# 2_MCU.net
KiCad netlist of a schematic drawn in Altium Designer
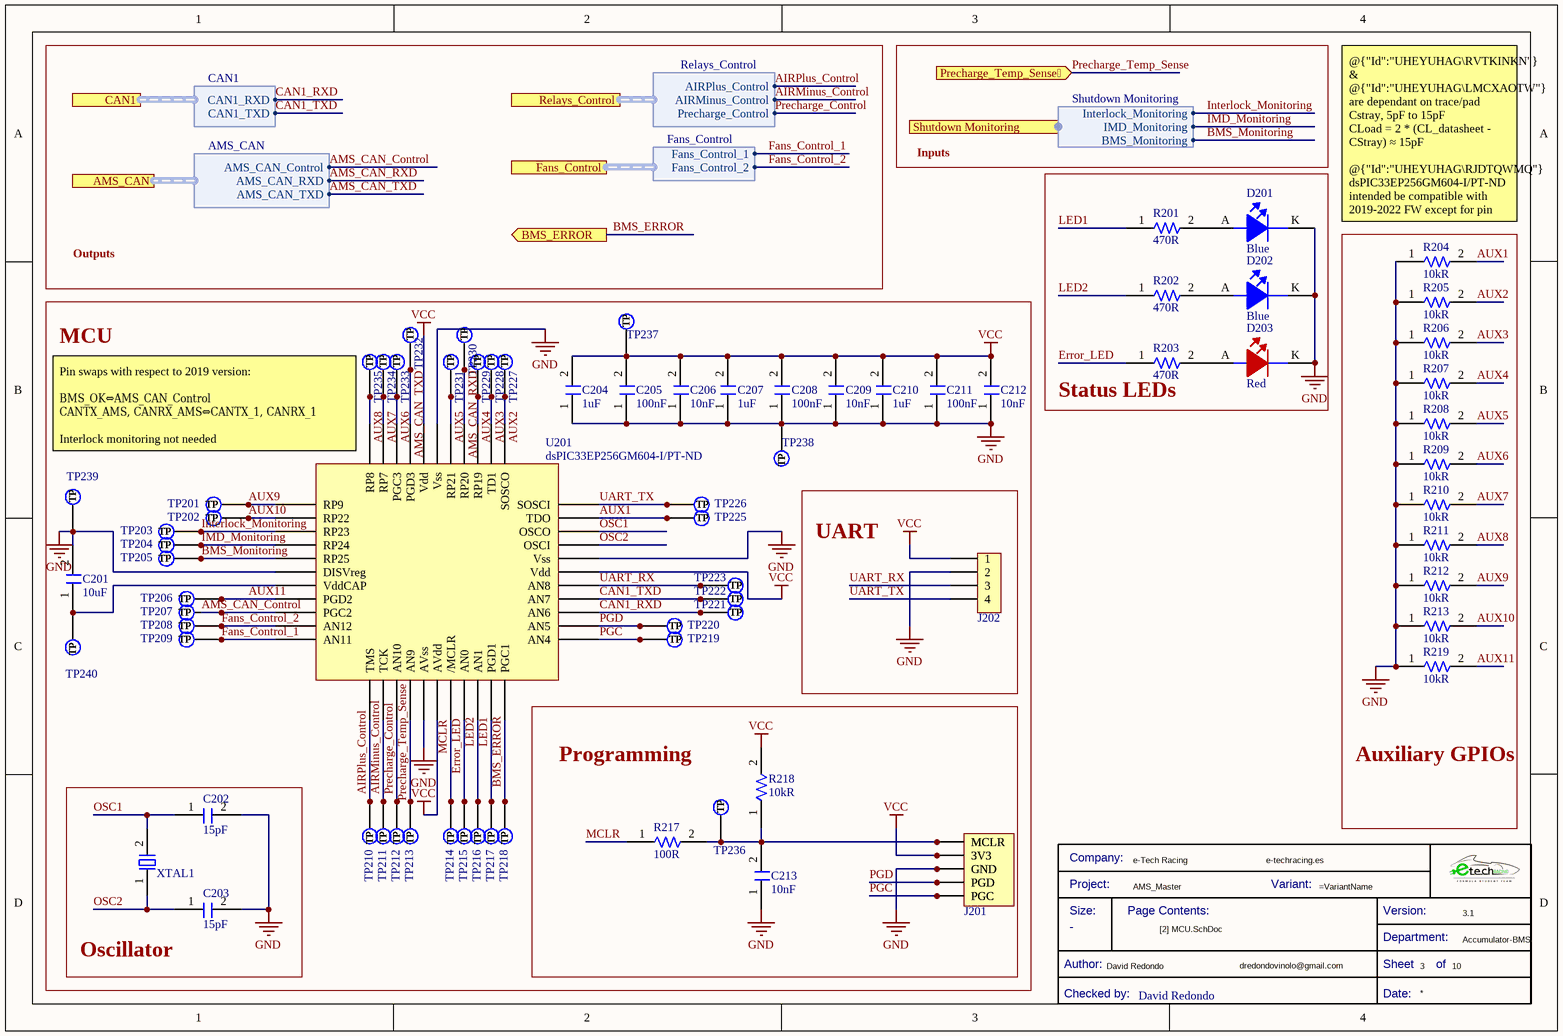
[diagram p0: [2] MCU.SchDoc]

(export (version "E")
  (design (tool "Eeschema 10.0.6"))
  (components
    (comp (ref "C201")
      (value "885012208018")
      (footprint "C1206FNPC-RW")
      (description "Cap, 10ΜF, 10V, 10%, X7R, 1206")
      (fields
        (field (name "TOLERANCE") "10%")
        (field (name "CAPACITANCE") "10uF")
        (field (name ".CREATOR") "GP")
      )
      (libsource (lib "Passives") (part "C10u-10V-1206FNPC-X7R"))
    )
    (comp (ref "C202")
      (value "885012007052")
      (footprint "C0805FNPC-R")
      (description "Cap, 15PF, 50V, 5%, C0G/NP0, 0805")
      (fields
        (field (name "TOLERANCE") "5%")
        (field (name "CAPACITANCE") "15pF")
        (field (name ".CREATOR") "DR")
      )
      (libsource (lib "Passives") (part "C15p-50V-0805FNPC-NP0"))
    )
    (comp (ref "C203")
      (value "885012007052")
      (footprint "C0805FNPC-R")
      (description "Cap, 15PF, 50V, 5%, C0G/NP0, 0805")
      (fields
        (field (name "TOLERANCE") "5%")
        (field (name "CAPACITANCE") "15pF")
        (field (name ".CREATOR") "DR")
      )
      (libsource (lib "Passives") (part "C15p-50V-0805FNPC-NP0"))
    )
    (comp (ref "C204")
      (value "885012207103")
      (footprint "C0805FNPC-R")
      (fields
        (field (name "TOLERANCE") "10%")
        (field (name "CAPACITANCE") "1uF")
        (field (name ".CREATOR") "GP")
      )
      (libsource (lib "Passives") (part "C1u-50V-0805FNPC-X7R"))
    )
    (comp (ref "C205")
      (value "885012207098")
      (footprint "C0805FNPC-R")
      (description "Cap, 0.1ΜF, 50V, 10%, X7R, 0805")
      (fields
        (field (name "TOLERANCE") "10%")
        (field (name "CAPACITANCE") "100nF")
        (field (name ".CREATOR") "DR")
      )
      (libsource (lib "Passives") (part "C100n-50V-0805FNPC-X7R"))
    )
    (comp (ref "C206")
      (value "885012207092")
      (footprint "C0805FNPC-R")
      (description "Cap, 0.01ΜF, 50V, 10%, X7R, 0805")
      (fields
        (field (name "TOLERANCE") "10%")
        (field (name "CAPACITANCE") "10nF")
        (field (name ".CREATOR") "DR")
      )
      (libsource (lib "Passives") (part "C10n-50V-0805FNPC-X7R"))
    )
    (comp (ref "C207")
      (value "885012207103")
      (footprint "C0805FNPC-R")
      (fields
        (field (name "TOLERANCE") "10%")
        (field (name "CAPACITANCE") "1uF")
        (field (name ".CREATOR") "GP")
      )
      (libsource (lib "Passives") (part "C1u-50V-0805FNPC-X7R"))
    )
    (comp (ref "C208")
      (value "885012207098")
      (footprint "C0805FNPC-R")
      (description "Cap, 0.1ΜF, 50V, 10%, X7R, 0805")
      (fields
        (field (name "TOLERANCE") "10%")
        (field (name "CAPACITANCE") "100nF")
        (field (name ".CREATOR") "DR")
      )
      (libsource (lib "Passives") (part "C100n-50V-0805FNPC-X7R"))
    )
    (comp (ref "C209")
      (value "885012207092")
      (footprint "C0805FNPC-R")
      (description "Cap, 0.01ΜF, 50V, 10%, X7R, 0805")
      (fields
        (field (name "TOLERANCE") "10%")
        (field (name "CAPACITANCE") "10nF")
        (field (name ".CREATOR") "DR")
      )
      (libsource (lib "Passives") (part "C10n-50V-0805FNPC-X7R"))
    )
    (comp (ref "C210")
      (value "885012207103")
      (footprint "C0805FNPC-R")
      (fields
        (field (name "TOLERANCE") "10%")
        (field (name "CAPACITANCE") "1uF")
        (field (name ".CREATOR") "GP")
      )
      (libsource (lib "Passives") (part "C1u-50V-0805FNPC-X7R"))
    )
    (comp (ref "C211")
      (value "885012207098")
      (footprint "C0805FNPC-R")
      (description "Cap, 0.1ΜF, 50V, 10%, X7R, 0805")
      (fields
        (field (name "TOLERANCE") "10%")
        (field (name "CAPACITANCE") "100nF")
        (field (name ".CREATOR") "DR")
      )
      (libsource (lib "Passives") (part "C100n-50V-0805FNPC-X7R"))
    )
    (comp (ref "C212")
      (value "885012207092")
      (footprint "C0805FNPC-R")
      (description "Cap, 0.01ΜF, 50V, 10%, X7R, 0805")
      (fields
        (field (name "TOLERANCE") "10%")
        (field (name "CAPACITANCE") "10nF")
        (field (name ".CREATOR") "DR")
      )
      (libsource (lib "Passives") (part "C10n-50V-0805FNPC-X7R"))
    )
    (comp (ref "C213")
      (value "885012207092")
      (footprint "C0805FNPC-R")
      (description "Cap, 0.01ΜF, 50V, 10%, X7R, 0805")
      (fields
        (field (name "TOLERANCE") "10%")
        (field (name "CAPACITANCE") "10nF")
        (field (name ".CREATOR") "DR")
      )
      (libsource (lib "Passives") (part "C10n-50V-0805FNPC-X7R"))
    )
    (comp (ref "D201")
      (value "150080BS75000")
      (footprint "LED_0805_WE")
      (description "LED BLUE CLEAR 0805 SMD")
      (fields (field (name "COLOR") "Blue") (field (name ".CREATOR") "GP"))
      (libsource (lib "Semiconductor") (part "LEDBS-0805-145"))
    )
    (comp (ref "D202")
      (value "150080BS75000")
      (footprint "LED_0805_WE")
      (description "LED BLUE CLEAR 0805 SMD")
      (fields (field (name "COLOR") "Blue") (field (name ".CREATOR") "GP"))
      (libsource (lib "Semiconductor") (part "LEDBS-0805-145"))
    )
    (comp (ref "D203")
      (value "150080RS75000")
      (footprint "LED_0805_WE")
      (description "0805(H=0.8mm) 红色 高亮 λD=625nm VF=2V IF=30mA PD=72mW")
      (fields (field (name "COLOR") "Red") (field (name ".CREATOR") "DR"))
      (libsource (lib "Semiconductor") (part "LEDRS-0805-150"))
    )
    (comp (ref "J201")
      (value "61300511121")
      (footprint "J_PinHeader_1x5")
      (description "THT Vertical Pin Header WR-PHD, Pitch 2.54 mm, Single Row, 5 pins")
      (fields (field (name "MANUFACTURER") "Molex") (field (name ".CREATOR") "GP"))
      (libsource (lib "Electromechanical") (part "J_Pickit3"))
    )
    (comp (ref "J202")
      (value "61300411121")
      (footprint "J_PinHeader_1x4")
      (description "CONN HEADER 4 POS 2.54")
      (fields (field (name ".CREATOR") "AC"))
      (libsource (lib "Electromechanical") (part "J_UART"))
    )
    (comp (ref "R201")
      (value "CR0805-FX-4700GLF")
      (footprint "R0805FTK")
      (description "Res Thick Film 0805 470 Ohm 1% 1/8W ±100ppm/°C Molded SMD SMD Paper Tape on Plastic Reel")
      (fields
        (field (name "TOLERANCE") "1%")
        (field (name "RESISTANCE") "470R")
        (field (name ".CREATOR") "DR")
      )
      (libsource (lib "Passives") (part "R470-0805FTK"))
    )
    (comp (ref "R202")
      (value "CR0805-FX-4700GLF")
      (footprint "R0805FTK")
      (description "Res Thick Film 0805 470 Ohm 1% 1/8W ±100ppm/°C Molded SMD SMD Paper Tape on Plastic Reel")
      (fields
        (field (name "TOLERANCE") "1%")
        (field (name "RESISTANCE") "470R")
        (field (name ".CREATOR") "DR")
      )
      (libsource (lib "Passives") (part "R470-0805FTK"))
    )
    (comp (ref "R203")
      (value "CR0805-FX-4700GLF")
      (footprint "R0805FTK")
      (description "Res Thick Film 0805 470 Ohm 1% 1/8W ±100ppm/°C Molded SMD SMD Paper Tape on Plastic Reel")
      (fields
        (field (name "TOLERANCE") "1%")
        (field (name "RESISTANCE") "470R")
        (field (name ".CREATOR") "DR")
      )
      (libsource (lib "Passives") (part "R470-0805FTK"))
    )
    (comp (ref "R204")
      (value "CR0805-JW-103ELF")
      (footprint "R0805FTK")
      (fields
        (field (name "TOLERANCE") "5%")
        (field (name "RESISTANCE") "10kR")
        (field (name ".CREATOR") "DR")
      )
      (libsource (lib "Passives") (part "R10k-0805FTK"))
    )
    (comp (ref "R205")
      (value "CR0805-JW-103ELF")
      (footprint "R0805FTK")
      (fields
        (field (name "TOLERANCE") "5%")
        (field (name "RESISTANCE") "10kR")
        (field (name ".CREATOR") "DR")
      )
      (libsource (lib "Passives") (part "R10k-0805FTK"))
    )
    (comp (ref "R206")
      (value "CR0805-JW-103ELF")
      (footprint "R0805FTK")
      (fields
        (field (name "TOLERANCE") "5%")
        (field (name "RESISTANCE") "10kR")
        (field (name ".CREATOR") "DR")
      )
      (libsource (lib "Passives") (part "R10k-0805FTK"))
    )
    (comp (ref "R207")
      (value "CR0805-JW-103ELF")
      (footprint "R0805FTK")
      (fields
        (field (name "TOLERANCE") "5%")
        (field (name "RESISTANCE") "10kR")
        (field (name ".CREATOR") "DR")
      )
      (libsource (lib "Passives") (part "R10k-0805FTK"))
    )
    (comp (ref "R208")
      (value "CR0805-JW-103ELF")
      (footprint "R0805FTK")
      (fields
        (field (name "TOLERANCE") "5%")
        (field (name "RESISTANCE") "10kR")
        (field (name ".CREATOR") "DR")
      )
      (libsource (lib "Passives") (part "R10k-0805FTK"))
    )
    (comp (ref "R209")
      (value "CR0805-JW-103ELF")
      (footprint "R0805FTK")
      (fields
        (field (name "TOLERANCE") "5%")
        (field (name "RESISTANCE") "10kR")
        (field (name ".CREATOR") "DR")
      )
      (libsource (lib "Passives") (part "R10k-0805FTK"))
    )
    (comp (ref "R210")
      (value "CR0805-JW-103ELF")
      (footprint "R0805FTK")
      (fields
        (field (name "TOLERANCE") "5%")
        (field (name "RESISTANCE") "10kR")
        (field (name ".CREATOR") "DR")
      )
      (libsource (lib "Passives") (part "R10k-0805FTK"))
    )
    (comp (ref "R211")
      (value "CR0805-JW-103ELF")
      (footprint "R0805FTK")
      (fields
        (field (name "TOLERANCE") "5%")
        (field (name "RESISTANCE") "10kR")
        (field (name ".CREATOR") "DR")
      )
      (libsource (lib "Passives") (part "R10k-0805FTK"))
    )
    (comp (ref "R212")
      (value "CR0805-JW-103ELF")
      (footprint "R0805FTK")
      (fields
        (field (name "TOLERANCE") "5%")
        (field (name "RESISTANCE") "10kR")
        (field (name ".CREATOR") "DR")
      )
      (libsource (lib "Passives") (part "R10k-0805FTK"))
    )
    (comp (ref "R213")
      (value "CR0805-JW-103ELF")
      (footprint "R0805FTK")
      (fields
        (field (name "TOLERANCE") "5%")
        (field (name "RESISTANCE") "10kR")
        (field (name ".CREATOR") "DR")
      )
      (libsource (lib "Passives") (part "R10k-0805FTK"))
    )
    (comp (ref "R217")
      (value "CR0805-FX-1000ELF")
      (footprint "R0805FTK")
      (description "Res Thick Film 0805 100 Ohm 1% 1/8W ±100ppm/°C Molded SMD SMD Paper Tape on Plastic Reel")
      (fields
        (field (name "TOLERANCE") "1%")
        (field (name "RESISTANCE") "100R")
        (field (name ".CREATOR") "DR")
      )
      (libsource (lib "Passives") (part "R100-0805FTK"))
    )
    (comp (ref "R218")
      (value "CR0805-JW-103ELF")
      (footprint "R0805FTK")
      (fields
        (field (name "TOLERANCE") "5%")
        (field (name "RESISTANCE") "10kR")
        (field (name ".CREATOR") "DR")
      )
      (libsource (lib "Passives") (part "R10k-0805FTK"))
    )
    (comp (ref "R219")
      (value "CR0805-JW-103ELF")
      (footprint "R0805FTK")
      (fields
        (field (name "TOLERANCE") "5%")
        (field (name "RESISTANCE") "10kR")
        (field (name ".CREATOR") "DR")
      )
      (libsource (lib "Passives") (part "R10k-0805FTK"))
    )
    (comp (ref "TP201")
      (value "TestPoint")
      (footprint "TestPoint")
      (description "Test Point 1x1 mm")
      (fields (field (name ".CREATOR") "GP") (field (name ".PCBCHECK") "GP") (field (name ".SCHCHECK") "GP"))
      (libsource (lib "e-Tech_Racing") (part "TestPoint"))
    )
    (comp (ref "TP202")
      (value "TestPoint")
      (footprint "TestPoint")
      (description "Test Point 1x1 mm")
      (fields (field (name ".CREATOR") "GP") (field (name ".PCBCHECK") "GP") (field (name ".SCHCHECK") "GP"))
      (libsource (lib "e-Tech_Racing") (part "TestPoint"))
    )
    (comp (ref "TP203")
      (value "TestPoint")
      (footprint "TestPoint")
      (description "Test Point 1x1 mm")
      (fields (field (name ".CREATOR") "GP") (field (name ".PCBCHECK") "GP") (field (name ".SCHCHECK") "GP"))
      (libsource (lib "e-Tech_Racing") (part "TestPoint"))
    )
    (comp (ref "TP204")
      (value "TestPoint")
      (footprint "TestPoint")
      (description "Test Point 1x1 mm")
      (fields (field (name ".CREATOR") "GP") (field (name ".PCBCHECK") "GP") (field (name ".SCHCHECK") "GP"))
      (libsource (lib "e-Tech_Racing") (part "TestPoint"))
    )
    (comp (ref "TP205")
      (value "TestPoint")
      (footprint "TestPoint")
      (description "Test Point 1x1 mm")
      (fields (field (name ".CREATOR") "GP") (field (name ".PCBCHECK") "GP") (field (name ".SCHCHECK") "GP"))
      (libsource (lib "e-Tech_Racing") (part "TestPoint"))
    )
    (comp (ref "TP206")
      (value "TestPoint")
      (footprint "TestPoint")
      (description "Test Point 1x1 mm")
      (fields (field (name ".CREATOR") "GP") (field (name ".PCBCHECK") "GP") (field (name ".SCHCHECK") "GP"))
      (libsource (lib "e-Tech_Racing") (part "TestPoint"))
    )
    (comp (ref "TP207")
      (value "TestPoint")
      (footprint "TestPoint")
      (description "Test Point 1x1 mm")
      (fields (field (name ".CREATOR") "GP") (field (name ".PCBCHECK") "GP") (field (name ".SCHCHECK") "GP"))
      (libsource (lib "e-Tech_Racing") (part "TestPoint"))
    )
    (comp (ref "TP208")
      (value "TestPoint")
      (footprint "TestPoint")
      (description "Test Point 1x1 mm")
      (fields (field (name ".CREATOR") "GP") (field (name ".PCBCHECK") "GP") (field (name ".SCHCHECK") "GP"))
      (libsource (lib "e-Tech_Racing") (part "TestPoint"))
    )
    (comp (ref "TP209")
      (value "TestPoint")
      (footprint "TestPoint")
      (description "Test Point 1x1 mm")
      (fields (field (name ".CREATOR") "GP") (field (name ".PCBCHECK") "GP") (field (name ".SCHCHECK") "GP"))
      (libsource (lib "e-Tech_Racing") (part "TestPoint"))
    )
    (comp (ref "TP210")
      (value "TestPoint")
      (footprint "TestPoint")
      (description "Test Point 1x1 mm")
      (fields (field (name ".CREATOR") "GP") (field (name ".PCBCHECK") "GP") (field (name ".SCHCHECK") "GP"))
      (libsource (lib "e-Tech_Racing") (part "TestPoint"))
    )
    (comp (ref "TP211")
      (value "TestPoint")
      (footprint "TestPoint")
      (description "Test Point 1x1 mm")
      (fields (field (name ".CREATOR") "GP") (field (name ".PCBCHECK") "GP") (field (name ".SCHCHECK") "GP"))
      (libsource (lib "e-Tech_Racing") (part "TestPoint"))
    )
    (comp (ref "TP212")
      (value "TestPoint")
      (footprint "TestPoint")
      (description "Test Point 1x1 mm")
      (fields (field (name ".CREATOR") "GP") (field (name ".PCBCHECK") "GP") (field (name ".SCHCHECK") "GP"))
      (libsource (lib "e-Tech_Racing") (part "TestPoint"))
    )
    (comp (ref "TP213")
      (value "TestPoint")
      (footprint "TestPoint")
      (description "Test Point 1x1 mm")
      (fields (field (name ".CREATOR") "GP") (field (name ".PCBCHECK") "GP") (field (name ".SCHCHECK") "GP"))
      (libsource (lib "e-Tech_Racing") (part "TestPoint"))
    )
    (comp (ref "TP214")
      (value "TestPoint")
      (footprint "TestPoint")
      (description "Test Point 1x1 mm")
      (fields (field (name ".CREATOR") "GP") (field (name ".PCBCHECK") "GP") (field (name ".SCHCHECK") "GP"))
      (libsource (lib "e-Tech_Racing") (part "TestPoint"))
    )
    (comp (ref "TP215")
      (value "TestPoint")
      (footprint "TestPoint")
      (description "Test Point 1x1 mm")
      (fields (field (name ".CREATOR") "GP") (field (name ".PCBCHECK") "GP") (field (name ".SCHCHECK") "GP"))
      (libsource (lib "e-Tech_Racing") (part "TestPoint"))
    )
    (comp (ref "TP216")
      (value "TestPoint")
      (footprint "TestPoint")
      (description "Test Point 1x1 mm")
      (fields (field (name ".CREATOR") "GP") (field (name ".PCBCHECK") "GP") (field (name ".SCHCHECK") "GP"))
      (libsource (lib "e-Tech_Racing") (part "TestPoint"))
    )
    (comp (ref "TP217")
      (value "TestPoint")
      (footprint "TestPoint")
      (description "Test Point 1x1 mm")
      (fields (field (name ".CREATOR") "GP") (field (name ".PCBCHECK") "GP") (field (name ".SCHCHECK") "GP"))
      (libsource (lib "e-Tech_Racing") (part "TestPoint"))
    )
    (comp (ref "TP218")
      (value "TestPoint")
      (footprint "TestPoint")
      (description "Test Point 1x1 mm")
      (fields (field (name ".CREATOR") "GP") (field (name ".PCBCHECK") "GP") (field (name ".SCHCHECK") "GP"))
      (libsource (lib "e-Tech_Racing") (part "TestPoint"))
    )
    (comp (ref "TP219")
      (value "TestPoint")
      (footprint "TestPoint")
      (description "Test Point 1x1 mm")
      (fields (field (name ".CREATOR") "GP") (field (name ".PCBCHECK") "GP") (field (name ".SCHCHECK") "GP"))
      (libsource (lib "e-Tech_Racing") (part "TestPoint"))
    )
    (comp (ref "TP220")
      (value "TestPoint")
      (footprint "TestPoint")
      (description "Test Point 1x1 mm")
      (fields (field (name ".CREATOR") "GP") (field (name ".PCBCHECK") "GP") (field (name ".SCHCHECK") "GP"))
      (libsource (lib "e-Tech_Racing") (part "TestPoint"))
    )
    (comp (ref "TP221")
      (value "TestPoint")
      (footprint "TestPoint")
      (description "Test Point 1x1 mm")
      (fields (field (name ".CREATOR") "GP") (field (name ".PCBCHECK") "GP") (field (name ".SCHCHECK") "GP"))
      (libsource (lib "e-Tech_Racing") (part "TestPoint"))
    )
    (comp (ref "TP222")
      (value "TestPoint")
      (footprint "TestPoint")
      (description "Test Point 1x1 mm")
      (fields (field (name ".CREATOR") "GP") (field (name ".PCBCHECK") "GP") (field (name ".SCHCHECK") "GP"))
      (libsource (lib "e-Tech_Racing") (part "TestPoint"))
    )
    (comp (ref "TP223")
      (value "TestPoint")
      (footprint "TestPoint")
      (description "Test Point 1x1 mm")
      (fields (field (name ".CREATOR") "GP") (field (name ".PCBCHECK") "GP") (field (name ".SCHCHECK") "GP"))
      (libsource (lib "e-Tech_Racing") (part "TestPoint"))
    )
    (comp (ref "TP225")
      (value "TestPoint")
      (footprint "TestPoint")
      (description "Test Point 1x1 mm")
      (fields (field (name ".CREATOR") "GP") (field (name ".PCBCHECK") "GP") (field (name ".SCHCHECK") "GP"))
      (libsource (lib "e-Tech_Racing") (part "TestPoint"))
    )
    (comp (ref "TP226")
      (value "TestPoint")
      (footprint "TestPoint")
      (description "Test Point 1x1 mm")
      (fields (field (name ".CREATOR") "GP") (field (name ".PCBCHECK") "GP") (field (name ".SCHCHECK") "GP"))
      (libsource (lib "e-Tech_Racing") (part "TestPoint"))
    )
    (comp (ref "TP227")
      (value "TestPoint")
      (footprint "TestPoint")
      (description "Test Point 1x1 mm")
      (fields (field (name ".CREATOR") "GP") (field (name ".PCBCHECK") "GP") (field (name ".SCHCHECK") "GP"))
      (libsource (lib "e-Tech_Racing") (part "TestPoint"))
    )
    (comp (ref "TP228")
      (value "TestPoint")
      (footprint "TestPoint")
      (description "Test Point 1x1 mm")
      (fields (field (name ".CREATOR") "GP") (field (name ".PCBCHECK") "GP") (field (name ".SCHCHECK") "GP"))
      (libsource (lib "e-Tech_Racing") (part "TestPoint"))
    )
    (comp (ref "TP229")
      (value "TestPoint")
      (footprint "TestPoint")
      (description "Test Point 1x1 mm")
      (fields (field (name ".CREATOR") "GP") (field (name ".PCBCHECK") "GP") (field (name ".SCHCHECK") "GP"))
      (libsource (lib "e-Tech_Racing") (part "TestPoint"))
    )
    (comp (ref "TP230")
      (value "TestPoint")
      (footprint "TestPoint")
      (description "Test Point 1x1 mm")
      (fields (field (name ".CREATOR") "GP") (field (name ".PCBCHECK") "GP") (field (name ".SCHCHECK") "GP"))
      (libsource (lib "e-Tech_Racing") (part "TestPoint"))
    )
    (comp (ref "TP231")
      (value "TestPoint")
      (footprint "TestPoint")
      (description "Test Point 1x1 mm")
      (fields (field (name ".CREATOR") "GP") (field (name ".PCBCHECK") "GP") (field (name ".SCHCHECK") "GP"))
      (libsource (lib "e-Tech_Racing") (part "TestPoint"))
    )
    (comp (ref "TP232")
      (value "TestPoint")
      (footprint "TestPoint")
      (description "Test Point 1x1 mm")
      (fields (field (name ".CREATOR") "GP") (field (name ".PCBCHECK") "GP") (field (name ".SCHCHECK") "GP"))
      (libsource (lib "e-Tech_Racing") (part "TestPoint"))
    )
    (comp (ref "TP233")
      (value "TestPoint")
      (footprint "TestPoint")
      (description "Test Point 1x1 mm")
      (fields (field (name ".CREATOR") "GP") (field (name ".PCBCHECK") "GP") (field (name ".SCHCHECK") "GP"))
      (libsource (lib "e-Tech_Racing") (part "TestPoint"))
    )
    (comp (ref "TP234")
      (value "TestPoint")
      (footprint "TestPoint")
      (description "Test Point 1x1 mm")
      (fields (field (name ".CREATOR") "GP") (field (name ".PCBCHECK") "GP") (field (name ".SCHCHECK") "GP"))
      (libsource (lib "e-Tech_Racing") (part "TestPoint"))
    )
    (comp (ref "TP235")
      (value "TestPoint")
      (footprint "TestPoint")
      (description "Test Point 1x1 mm")
      (fields (field (name ".CREATOR") "GP") (field (name ".PCBCHECK") "GP") (field (name ".SCHCHECK") "GP"))
      (libsource (lib "e-Tech_Racing") (part "TestPoint"))
    )
    (comp (ref "TP236")
      (value "TestPoint")
      (footprint "TestPoint")
      (description "Test Point 1x1 mm")
      (fields (field (name ".CREATOR") "GP") (field (name ".PCBCHECK") "GP") (field (name ".SCHCHECK") "GP"))
      (libsource (lib "e-Tech_Racing") (part "TestPoint"))
    )
    (comp (ref "TP237")
      (value "TestPoint")
      (footprint "TestPoint")
      (description "Test Point 1x1 mm")
      (fields (field (name ".CREATOR") "GP") (field (name ".PCBCHECK") "GP") (field (name ".SCHCHECK") "GP"))
      (libsource (lib "e-Tech_Racing") (part "TestPoint"))
    )
    (comp (ref "TP238")
      (value "TestPoint")
      (footprint "TestPoint")
      (description "Test Point 1x1 mm")
      (fields (field (name ".CREATOR") "GP") (field (name ".PCBCHECK") "GP") (field (name ".SCHCHECK") "GP"))
      (libsource (lib "e-Tech_Racing") (part "TestPoint"))
    )
    (comp (ref "TP239")
      (value "TestPoint")
      (footprint "TestPoint")
      (description "Test Point 1x1 mm")
      (fields (field (name ".CREATOR") "GP") (field (name ".PCBCHECK") "GP") (field (name ".SCHCHECK") "GP"))
      (libsource (lib "e-Tech_Racing") (part "TestPoint"))
    )
    (comp (ref "TP240")
      (value "TestPoint")
      (footprint "TestPoint")
      (description "Test Point 1x1 mm")
      (fields (field (name ".CREATOR") "GP") (field (name ".PCBCHECK") "GP") (field (name ".SCHCHECK") "GP"))
      (libsource (lib "e-Tech_Racing") (part "TestPoint"))
    )
    (comp (ref "U201")
      (value "dsPIC33EP256GM604-I/PT")
      (footprint "U_dsPIC33EP256GM604-I/PT")
      (description "16-bit MCU/DSC, 256 KB, 32768 Bytes, 70 MHz, 3 to 3.6V, TQFP-44, RoHS")
      (fields
        (field (name "SUPPLIER PART NUMBER 1") "dsPIC33EP256GM604-I/PT-ND")
        (field (name ".CREATOR") "DR")
      )
      (libsource (lib "Integrated circuits") (part "U_dsPIC33EP256GM604-I/PT"))
    )
    (comp (ref "XTAL1")
      (value "830028710")
      (footprint "XTAL20M_SMD")
      (description "830028710, 20 MHz")
      (fields (field (name "MANUFACTURER") "Würth Elektronik") (field (name ".CREATOR") "GP"))
      (libsource (lib "Passives") (part "XTAL20M_SMD"))
    )
  )
  (nets
    (net (code "7") (name "/AIRMinus_Control") (class "Default")
      (node (ref "TP211") (pin "1") (pinfunction "TP_1") (pintype "passive"))
      (node (ref "U201") (pin "13") (pinfunction "TCK_13") (pintype "passive"))
    )
    (net (code "8") (name "/AIRPlus_Control") (class "Default")
      (node (ref "TP210") (pin "1") (pinfunction "TP_1") (pintype "passive"))
      (node (ref "U201") (pin "12") (pinfunction "TMS_12") (pintype "passive"))
    )
    (net (code "9") (name "/AMS_CAN_Control") (class "Default")
      (node (ref "TP207") (pin "1") (pinfunction "TP_1") (pintype "passive"))
      (node (ref "U201") (pin "9") (pinfunction "PGC2_9") (pintype "passive"))
    )
    (net (code "10") (name "/AMS_CAN_RXD") (class "Default")
      (node (ref "TP230") (pin "1") (pinfunction "TP_1") (pintype "passive"))
      (node (ref "U201") (pin "37") (pinfunction "RP20_37") (pintype "passive"))
    )
    (net (code "11") (name "/AMS_CAN_TXD") (class "Default")
      (node (ref "TP232") (pin "1") (pinfunction "TP_1") (pintype "passive"))
      (node (ref "U201") (pin "41") (pinfunction "PGD3_41") (pintype "passive"))
    )
    (net (code "12") (name "/AUX1") (class "Default")
      (node (ref "R204") (pin "2") (pinfunction "2_2") (pintype "passive"))
      (node (ref "TP225") (pin "1") (pinfunction "TP_1") (pintype "passive"))
      (node (ref "U201") (pin "32") (pinfunction "TDO_32") (pintype "passive"))
    )
    (net (code "13") (name "/AUX2") (class "Default")
      (node (ref "R205") (pin "2") (pinfunction "2_2") (pintype "passive"))
      (node (ref "TP227") (pin "1") (pinfunction "TP_1") (pintype "passive"))
      (node (ref "U201") (pin "34") (pinfunction "SOSCO_34") (pintype "passive"))
    )
    (net (code "14") (name "/AUX3") (class "Default")
      (node (ref "R206") (pin "2") (pinfunction "2_2") (pintype "passive"))
      (node (ref "TP228") (pin "1") (pinfunction "TP_1") (pintype "passive"))
      (node (ref "U201") (pin "35") (pinfunction "TD1_35") (pintype "passive"))
    )
    (net (code "15") (name "/AUX4") (class "Default")
      (node (ref "R207") (pin "2") (pinfunction "2_2") (pintype "passive"))
      (node (ref "TP229") (pin "1") (pinfunction "TP_1") (pintype "passive"))
      (node (ref "U201") (pin "36") (pinfunction "RP19_36") (pintype "passive"))
    )
    (net (code "16") (name "/AUX5") (class "Default")
      (node (ref "R208") (pin "2") (pinfunction "2_2") (pintype "passive"))
      (node (ref "TP231") (pin "1") (pinfunction "TP_1") (pintype "passive"))
      (node (ref "U201") (pin "38") (pinfunction "RP21_38") (pintype "passive"))
    )
    (net (code "17") (name "/AUX6") (class "Default")
      (node (ref "R209") (pin "2") (pinfunction "2_2") (pintype "passive"))
      (node (ref "TP233") (pin "1") (pinfunction "TP_1") (pintype "passive"))
      (node (ref "U201") (pin "42") (pinfunction "PGC3_42") (pintype "passive"))
    )
    (net (code "18") (name "/AUX7") (class "Default")
      (node (ref "R210") (pin "2") (pinfunction "2_2") (pintype "passive"))
      (node (ref "TP234") (pin "1") (pinfunction "TP_1") (pintype "passive"))
      (node (ref "U201") (pin "43") (pinfunction "RP7_43") (pintype "passive"))
    )
    (net (code "19") (name "/AUX8") (class "Default")
      (node (ref "R211") (pin "2") (pinfunction "2_2") (pintype "passive"))
      (node (ref "TP235") (pin "1") (pinfunction "TP_1") (pintype "passive"))
      (node (ref "U201") (pin "44") (pinfunction "RP8_44") (pintype "passive"))
    )
    (net (code "20") (name "/AUX9") (class "Default")
      (node (ref "R212") (pin "2") (pinfunction "2_2") (pintype "passive"))
      (node (ref "TP201") (pin "1") (pinfunction "TP_1") (pintype "passive"))
      (node (ref "U201") (pin "1") (pinfunction "RP9_1") (pintype "passive"))
    )
    (net (code "21") (name "/AUX10") (class "Default")
      (node (ref "R213") (pin "2") (pinfunction "2_2") (pintype "passive"))
      (node (ref "TP202") (pin "1") (pinfunction "TP_1") (pintype "passive"))
      (node (ref "U201") (pin "2") (pinfunction "RP22_2") (pintype "passive"))
    )
    (net (code "22") (name "/AUX11") (class "Default")
      (node (ref "R219") (pin "2") (pinfunction "2_2") (pintype "passive"))
      (node (ref "TP206") (pin "1") (pinfunction "TP_1") (pintype "passive"))
      (node (ref "U201") (pin "8") (pinfunction "PGD2_8") (pintype "passive"))
    )
    (net (code "23") (name "/BMS_ERROR") (class "Default")
      (node (ref "TP218") (pin "1") (pinfunction "TP_1") (pintype "passive"))
      (node (ref "U201") (pin "22") (pinfunction "PGC1_22") (pintype "passive"))
    )
    (net (code "24") (name "/BMS_Monitoring") (class "Default")
      (node (ref "TP205") (pin "1") (pinfunction "TP_1") (pintype "passive"))
      (node (ref "U201") (pin "5") (pinfunction "RP25_5") (pintype "passive"))
    )
    (net (code "25") (name "/CAN1_RXD") (class "Default")
      (node (ref "TP221") (pin "1") (pinfunction "TP_1") (pintype "passive"))
      (node (ref "U201") (pin "25") (pinfunction "AN6_25") (pintype "passive"))
    )
    (net (code "26") (name "/CAN1_TXD") (class "Default")
      (node (ref "TP222") (pin "1") (pinfunction "TP_1") (pintype "passive"))
      (node (ref "U201") (pin "26") (pinfunction "AN7_26") (pintype "passive"))
    )
    (net (code "27") (name "/Error_LED") (class "Default")
      (node (ref "R203") (pin "1") (pinfunction "1_1") (pintype "passive"))
      (node (ref "TP215") (pin "1") (pinfunction "TP_1") (pintype "passive"))
      (node (ref "U201") (pin "19") (pinfunction "AN0_19") (pintype "passive"))
    )
    (net (code "28") (name "/Fans_Control_1") (class "Default")
      (node (ref "TP209") (pin "1") (pinfunction "TP_1") (pintype "passive"))
      (node (ref "U201") (pin "11") (pinfunction "AN11_11") (pintype "passive"))
    )
    (net (code "29") (name "/Fans_Control_2") (class "Default")
      (node (ref "TP208") (pin "1") (pinfunction "TP_1") (pintype "passive"))
      (node (ref "U201") (pin "10") (pinfunction "AN12_10") (pintype "passive"))
    )
    (net (code "30") (name "/IMD_Monitoring") (class "Default")
      (node (ref "TP204") (pin "1") (pinfunction "TP_1") (pintype "passive"))
      (node (ref "U201") (pin "4") (pinfunction "RP24_4") (pintype "passive"))
    )
    (net (code "31") (name "/Interlock_Monitoring") (class "Default")
      (node (ref "TP203") (pin "1") (pinfunction "TP_1") (pintype "passive"))
      (node (ref "U201") (pin "3") (pinfunction "RP23_3") (pintype "passive"))
    )
    (net (code "32") (name "/LED1") (class "Default")
      (node (ref "R201") (pin "1") (pinfunction "1_1") (pintype "passive"))
      (node (ref "TP217") (pin "1") (pinfunction "TP_1") (pintype "passive"))
      (node (ref "U201") (pin "21") (pinfunction "PGD1_21") (pintype "passive"))
    )
    (net (code "33") (name "/LED2") (class "Default")
      (node (ref "R202") (pin "1") (pinfunction "1_1") (pintype "passive"))
      (node (ref "TP216") (pin "1") (pinfunction "TP_1") (pintype "passive"))
      (node (ref "U201") (pin "20") (pinfunction "AN1_20") (pintype "passive"))
    )
    (net (code "34") (name "/MCLR") (class "Default")
      (node (ref "R217") (pin "1") (pinfunction "1_1") (pintype "passive"))
      (node (ref "TP214") (pin "1") (pinfunction "TP_1") (pintype "passive"))
      (node (ref "U201") (pin "18") (pinfunction "/MCLR_18") (pintype "passive"))
    )
    (net (code "35") (name "/OSC1") (class "Default")
      (node (ref "C202") (pin "1") (pinfunction "1_1") (pintype "passive"))
      (node (ref "U201") (pin "31") (pinfunction "OSCO_31") (pintype "passive"))
      (node (ref "XTAL1") (pin "2") (pinfunction "2_2") (pintype "passive"))
    )
    (net (code "36") (name "/OSC2") (class "Default")
      (node (ref "C203") (pin "1") (pinfunction "1_1") (pintype "passive"))
      (node (ref "U201") (pin "30") (pinfunction "OSCI_30") (pintype "passive"))
      (node (ref "XTAL1") (pin "1") (pinfunction "1_1") (pintype "passive"))
    )
    (net (code "37") (name "/PGC") (class "Default")
      (node (ref "J201") (pin "5") (pinfunction "PGC_5") (pintype "passive"))
      (node (ref "TP219") (pin "1") (pinfunction "TP_1") (pintype "passive"))
      (node (ref "U201") (pin "23") (pinfunction "AN4_23") (pintype "passive"))
    )
    (net (code "38") (name "/PGD") (class "Default")
      (node (ref "J201") (pin "4") (pinfunction "PGD_4") (pintype "passive"))
      (node (ref "TP220") (pin "1") (pinfunction "TP_1") (pintype "passive"))
      (node (ref "U201") (pin "24") (pinfunction "AN5_24") (pintype "passive"))
    )
    (net (code "39") (name "/Precharge_Control") (class "Default")
      (node (ref "TP212") (pin "1") (pinfunction "TP_1") (pintype "passive"))
      (node (ref "U201") (pin "14") (pinfunction "AN10_14") (pintype "passive"))
    )
    (net (code "40") (name "/Precharge_Temp_Sense") (class "Default")
      (node (ref "TP213") (pin "1") (pinfunction "TP_1") (pintype "passive"))
      (node (ref "U201") (pin "15") (pinfunction "AN9_15") (pintype "passive"))
    )
    (net (code "41") (name "/UART_RX") (class "Default")
      (node (ref "J202") (pin "3") (pinfunction "3_3") (pintype "passive"))
      (node (ref "TP223") (pin "1") (pinfunction "TP_1") (pintype "passive"))
      (node (ref "U201") (pin "27") (pinfunction "AN8_27") (pintype "passive"))
    )
    (net (code "42") (name "/UART_TX") (class "Default")
      (node (ref "J202") (pin "4") (pinfunction "4_4") (pintype "passive"))
      (node (ref "TP226") (pin "1") (pinfunction "TP_1") (pintype "passive"))
      (node (ref "U201") (pin "33") (pinfunction "SOSCI_33") (pintype "passive"))
    )
    (net (code "48") (name "GND") (class "Default")
      (node (ref "C201") (pin "2") (pinfunction "2_2") (pintype "passive"))
      (node (ref "C202") (pin "2") (pinfunction "2_2") (pintype "passive"))
      (node (ref "C203") (pin "2") (pinfunction "2_2") (pintype "passive"))
      (node (ref "C204") (pin "1") (pinfunction "1_1") (pintype "passive"))
      (node (ref "C205") (pin "1") (pinfunction "1_1") (pintype "passive"))
      (node (ref "C206") (pin "1") (pinfunction "1_1") (pintype "passive"))
      (node (ref "C207") (pin "1") (pinfunction "1_1") (pintype "passive"))
      (node (ref "C208") (pin "1") (pinfunction "1_1") (pintype "passive"))
      (node (ref "C209") (pin "1") (pinfunction "1_1") (pintype "passive"))
      (node (ref "C210") (pin "1") (pinfunction "1_1") (pintype "passive"))
      (node (ref "C211") (pin "1") (pinfunction "1_1") (pintype "passive"))
      (node (ref "C212") (pin "1") (pinfunction "1_1") (pintype "passive"))
      (node (ref "C213") (pin "1") (pinfunction "1_1") (pintype "passive"))
      (node (ref "D201") (pin "K") (pinfunction "K_K") (pintype "passive"))
      (node (ref "D202") (pin "K") (pinfunction "K_K") (pintype "passive"))
      (node (ref "D203") (pin "K") (pinfunction "K_K") (pintype "passive"))
      (node (ref "J201") (pin "3") (pinfunction "GND_3") (pintype "passive"))
      (node (ref "J202") (pin "2") (pinfunction "2_2") (pintype "passive"))
      (node (ref "R204") (pin "1") (pinfunction "1_1") (pintype "passive"))
      (node (ref "R205") (pin "1") (pinfunction "1_1") (pintype "passive"))
      (node (ref "R206") (pin "1") (pinfunction "1_1") (pintype "passive"))
      (node (ref "R207") (pin "1") (pinfunction "1_1") (pintype "passive"))
      (node (ref "R208") (pin "1") (pinfunction "1_1") (pintype "passive"))
      (node (ref "R209") (pin "1") (pinfunction "1_1") (pintype "passive"))
      (node (ref "R210") (pin "1") (pinfunction "1_1") (pintype "passive"))
      (node (ref "R211") (pin "1") (pinfunction "1_1") (pintype "passive"))
      (node (ref "R212") (pin "1") (pinfunction "1_1") (pintype "passive"))
      (node (ref "R213") (pin "1") (pinfunction "1_1") (pintype "passive"))
      (node (ref "R219") (pin "1") (pinfunction "1_1") (pintype "passive"))
      (node (ref "TP238") (pin "1") (pinfunction "TP_1") (pintype "passive"))
      (node (ref "TP239") (pin "1") (pinfunction "TP_1") (pintype "passive"))
      (node (ref "U201") (pin "16") (pinfunction "AVss_16") (pintype "passive"))
      (node (ref "U201") (pin "29") (pinfunction "Vss_29") (pintype "passive"))
      (node (ref "U201") (pin "39") (pinfunction "Vss_39") (pintype "passive"))
      (node (ref "U201") (pin "6") (pinfunction "DISVreg_6") (pintype "passive"))
    )
    (net (code "49") (name "Net-(D201-PadA)") (class "Default")
      (node (ref "D201") (pin "A") (pinfunction "A_A") (pintype "passive"))
      (node (ref "R201") (pin "2") (pinfunction "2_2") (pintype "passive"))
    )
    (net (code "50") (name "Net-(D202-PadA)") (class "Default")
      (node (ref "D202") (pin "A") (pinfunction "A_A") (pintype "passive"))
      (node (ref "R202") (pin "2") (pinfunction "2_2") (pintype "passive"))
    )
    (net (code "51") (name "Net-(D203-PadA)") (class "Default")
      (node (ref "D203") (pin "A") (pinfunction "A_A") (pintype "passive"))
      (node (ref "R203") (pin "2") (pinfunction "2_2") (pintype "passive"))
    )
    (net (code "52") (name "Net-(J201-MCLR)") (class "Default")
      (node (ref "C213") (pin "2") (pinfunction "2_2") (pintype "passive"))
      (node (ref "J201") (pin "1") (pinfunction "MCLR_1") (pintype "passive"))
      (node (ref "R217") (pin "2") (pinfunction "2_2") (pintype "passive"))
      (node (ref "R218") (pin "1") (pinfunction "1_1") (pintype "passive"))
      (node (ref "TP236") (pin "1") (pinfunction "TP_1") (pintype "passive"))
    )
    (net (code "53") (name "Net-(TP240-TP)") (class "Default")
      (node (ref "C201") (pin "1") (pinfunction "1_1") (pintype "passive"))
      (node (ref "TP240") (pin "1") (pinfunction "TP_1") (pintype "passive"))
      (node (ref "U201") (pin "7") (pinfunction "VddCAP_7") (pintype "passive"))
    )
    (net (code "54") (name "VCC") (class "Default")
      (node (ref "C204") (pin "2") (pinfunction "2_2") (pintype "passive"))
      (node (ref "C205") (pin "2") (pinfunction "2_2") (pintype "passive"))
      (node (ref "C206") (pin "2") (pinfunction "2_2") (pintype "passive"))
      (node (ref "C207") (pin "2") (pinfunction "2_2") (pintype "passive"))
      (node (ref "C208") (pin "2") (pinfunction "2_2") (pintype "passive"))
      (node (ref "C209") (pin "2") (pinfunction "2_2") (pintype "passive"))
      (node (ref "C210") (pin "2") (pinfunction "2_2") (pintype "passive"))
      (node (ref "C211") (pin "2") (pinfunction "2_2") (pintype "passive"))
      (node (ref "C212") (pin "2") (pinfunction "2_2") (pintype "passive"))
      (node (ref "J201") (pin "2") (pinfunction "3V3_2") (pintype "passive"))
      (node (ref "J202") (pin "1") (pinfunction "1_1") (pintype "passive"))
      (node (ref "R218") (pin "2") (pinfunction "2_2") (pintype "passive"))
      (node (ref "TP237") (pin "1") (pinfunction "TP_1") (pintype "passive"))
      (node (ref "U201") (pin "17") (pinfunction "AVdd_17") (pintype "passive"))
      (node (ref "U201") (pin "28") (pinfunction "Vdd_28") (pintype "passive"))
      (node (ref "U201") (pin "40") (pinfunction "Vdd_40") (pintype "passive"))
    )
  )
)
